# 1-power.net
KiCad netlist of a schematic drawn in Altium Designer
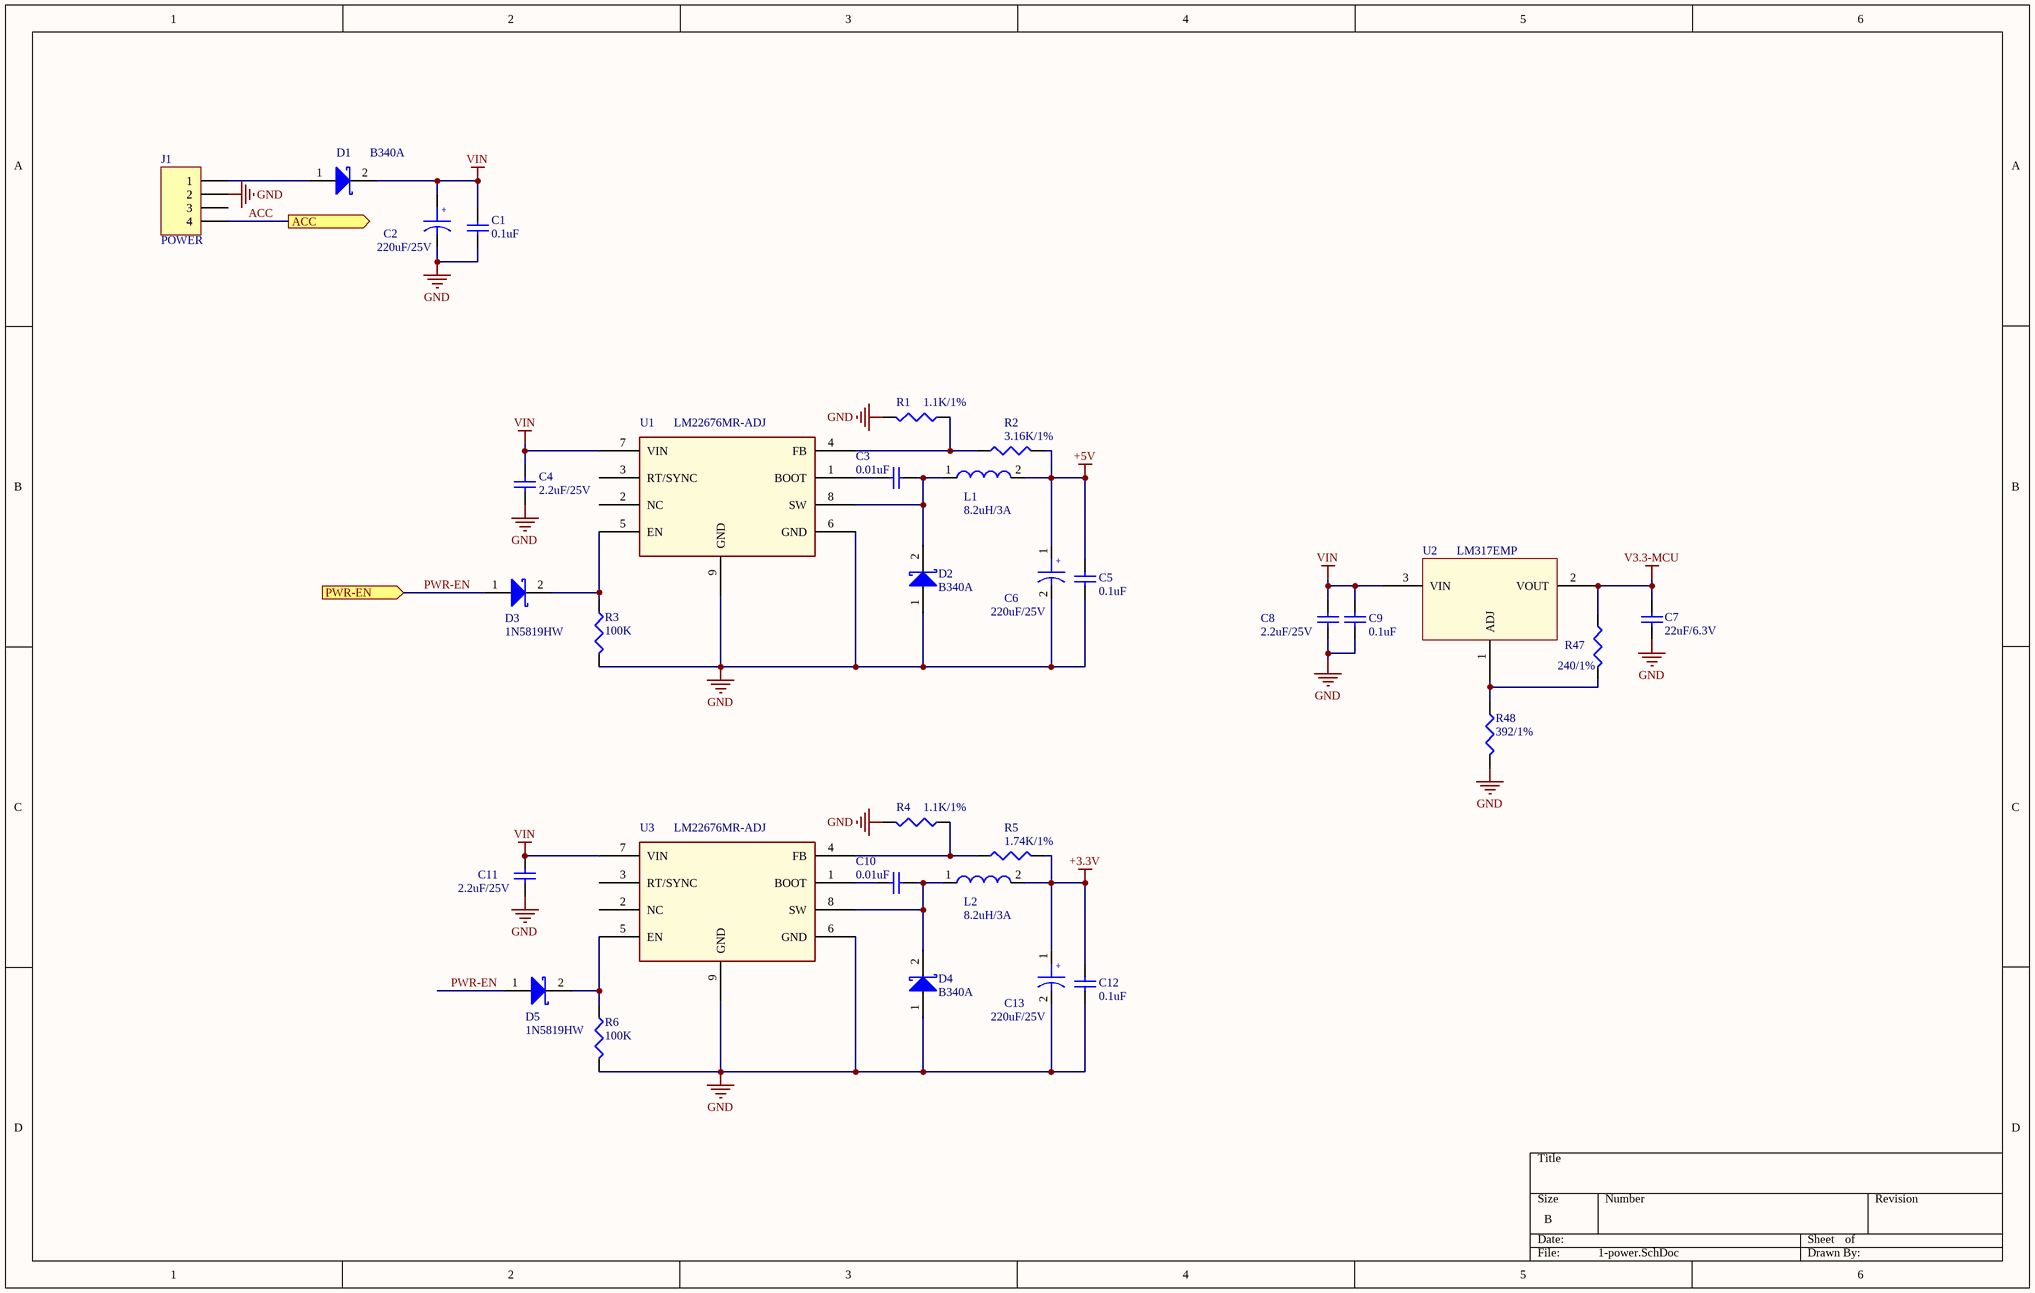
[diagram p0: 1-power.SchDoc]

(export (version "E")
  (design (tool "Eeschema 10.0.6"))
  (components
    (comp (ref "C1")
      (value "0.1uF")
      (footprint "0603")
      (description "Capacitor")
      (fields (field (name "PUBLISHER") "Altium Limited"))
      (libsource (lib "Miscellaneous Devices") (part "Cap"))
    )
    (comp (ref "C2") (value "220uF/25V") (libsource (lib "") (part "CAP WP_1")))
    (comp (ref "C3")
      (value "0.01uF")
      (footprint "0603")
      (description "Capacitor")
      (fields (field (name "PUBLISHER") "Altium Limited"))
      (libsource (lib "Miscellaneous Devices") (part "Cap"))
    )
    (comp (ref "C4")
      (value "2.2uF/25V")
      (footprint "1210")
      (description "Capacitor")
      (fields (field (name "PUBLISHER") "Altium Limited"))
      (libsource (lib "Miscellaneous Devices") (part "Cap"))
    )
    (comp (ref "C5")
      (value "0.1uF")
      (footprint "0603")
      (description "Capacitor")
      (fields (field (name "PUBLISHER") "Altium Limited"))
      (libsource (lib "Miscellaneous Devices") (part "Cap"))
    )
    (comp (ref "C6") (value "220uF/25V") (libsource (lib "*") (part "CAP WP")))
    (comp (ref "C7")
      (value "22uF/6.3V")
      (footprint "1206")
      (description "Capacitor")
      (fields (field (name "PUBLISHER") "Altium Limited"))
      (libsource (lib "Miscellaneous Devices") (part "Cap"))
    )
    (comp (ref "C8")
      (value "2.2uF/25V")
      (footprint "1210")
      (description "Capacitor")
      (fields (field (name "PUBLISHER") "Altium Limited"))
      (libsource (lib "Miscellaneous Devices") (part "Cap"))
    )
    (comp (ref "C9")
      (value "0.1uF")
      (footprint "0603")
      (description "Capacitor")
      (fields (field (name "PUBLISHER") "Altium Limited"))
      (libsource (lib "Miscellaneous Devices") (part "Cap"))
    )
    (comp (ref "C10")
      (value "0.01uF")
      (footprint "0603")
      (description "Capacitor")
      (fields (field (name "PUBLISHER") "Altium Limited"))
      (libsource (lib "Miscellaneous Devices") (part "Cap"))
    )
    (comp (ref "C11")
      (value "2.2uF/25V")
      (footprint "1210")
      (description "Capacitor")
      (fields (field (name "PUBLISHER") "Altium Limited"))
      (libsource (lib "Miscellaneous Devices") (part "Cap"))
    )
    (comp (ref "C12")
      (value "0.1uF")
      (footprint "0603")
      (description "Capacitor")
      (fields (field (name "PUBLISHER") "Altium Limited"))
      (libsource (lib "Miscellaneous Devices") (part "Cap"))
    )
    (comp (ref "C13") (value "220uF/25V") (libsource (lib "*") (part "CAP WP")))
    (comp (ref "D1")
      (value "B340A")
      (footprint "B320A")
      (description "Schottky Rectifier")
      (libsource (lib "Miscellaneous Devices") (part "Diode 11DQ03"))
    )
    (comp (ref "D2")
      (value "B340A")
      (footprint "B320A")
      (description "Schottky Rectifier")
      (libsource (lib "Miscellaneous Devices") (part "Diode 11DQ03"))
    )
    (comp (ref "D3")
      (value "1N5819HW")
      (footprint "1N5819")
      (description "Schottky Rectifier")
      (libsource (lib "Miscellaneous Devices") (part "Diode 11DQ03"))
    )
    (comp (ref "D4")
      (value "B340A")
      (footprint "B320A")
      (description "Schottky Rectifier")
      (libsource (lib "Miscellaneous Devices") (part "Diode 11DQ03"))
    )
    (comp (ref "D5")
      (value "1N5819HW")
      (footprint "1N5819")
      (description "Schottky Rectifier")
      (libsource (lib "Miscellaneous Devices") (part "Diode 11DQ03"))
    )
    (comp (ref "J1")
      (value "POWER")
      (footprint "3030WV-F-2*2P")
      (description "Header, 4-Pin")
      (fields (field (name "PUBLISHER") "Altium Limited"))
      (libsource (lib "Miscellaneous Connectors") (part "Header 4"))
    )
    (comp (ref "L1")
      (value "8.2uH/3A")
      (footprint "IND_8.2UH_3A")
      (fields (field (name "PART NUMBER") "SH00000AJ00"))
      (libsource (lib "*") (part "4.7UH_CDH2D09BNP-4R7MC_0.7A_20%"))
    )
    (comp (ref "L2")
      (value "8.2uH/3A")
      (footprint "IND_8.2UH_3A")
      (fields (field (name "PART NUMBER") "SH00000AJ00"))
      (libsource (lib "*") (part "4.7UH_CDH2D09BNP-4R7MC_0.7A_20%"))
    )
    (comp (ref "R1")
      (value "1.1K/1%")
      (footprint "0603")
      (description "Resistor")
      (fields (field (name "PUBLISHER") "Altium Limited"))
      (libsource (lib "Miscellaneous Devices") (part "Res3"))
    )
    (comp (ref "R2")
      (value "3.16K/1%")
      (footprint "0603")
      (description "Resistor")
      (fields (field (name "PUBLISHER") "Altium Limited"))
      (libsource (lib "Miscellaneous Devices") (part "Res3"))
    )
    (comp (ref "R3")
      (value "100K")
      (footprint "0603")
      (description "Resistor")
      (fields (field (name "PUBLISHER") "Altium Limited"))
      (libsource (lib "Miscellaneous Devices") (part "Res3"))
    )
    (comp (ref "R4")
      (value "1.1K/1%")
      (footprint "0603")
      (description "Resistor")
      (fields (field (name "PUBLISHER") "Altium Limited"))
      (libsource (lib "Miscellaneous Devices") (part "Res3"))
    )
    (comp (ref "R5")
      (value "1.74K/1%")
      (footprint "0603")
      (description "Resistor")
      (fields (field (name "PUBLISHER") "Altium Limited"))
      (libsource (lib "Miscellaneous Devices") (part "Res3"))
    )
    (comp (ref "R6")
      (value "100K")
      (footprint "0603")
      (description "Resistor")
      (fields (field (name "PUBLISHER") "Altium Limited"))
      (libsource (lib "Miscellaneous Devices") (part "Res3"))
    )
    (comp (ref "R47")
      (value "240/1%")
      (footprint "0603")
      (description "Resistor")
      (fields (field (name "PUBLISHER") "Altium Limited"))
      (libsource (lib "Miscellaneous Devices") (part "Res3"))
    )
    (comp (ref "R48")
      (value "392/1%")
      (footprint "0603")
      (description "Resistor")
      (fields (field (name "PUBLISHER") "Altium Limited"))
      (libsource (lib "Miscellaneous Devices") (part "Res3"))
    )
    (comp (ref "U1") (value "LM22676MR-ADJ") (libsource (lib "*") (part "LM22670_0")))
    (comp (ref "U2") (value "LM317EMP") (footprint "SOT-223") (libsource (lib "Schlib") (part "LM317EMP")))
    (comp (ref "U3") (value "LM22676MR-ADJ") (libsource (lib "*") (part "LM22670_0")))
  )
  (nets
    (net (code "1") (name "+3.3V") (class "Default")
      (node (ref "C12") (pin "2") (pinfunction "2_2") (pintype "passive"))
      (node (ref "C13") (pin "1") (pinfunction "1_1") (pintype "passive"))
      (node (ref "L2") (pin "2") (pinfunction "2_2") (pintype "passive"))
      (node (ref "R5") (pin "2") (pinfunction "2_2") (pintype "passive"))
    )
    (net (code "2") (name "+5V") (class "Default")
      (node (ref "C5") (pin "2") (pinfunction "2_2") (pintype "passive"))
      (node (ref "C6") (pin "1") (pinfunction "1_1") (pintype "passive"))
      (node (ref "L1") (pin "2") (pinfunction "2_2") (pintype "passive"))
      (node (ref "R2") (pin "2") (pinfunction "2_2") (pintype "passive"))
    )
    (net (code "3") (name "/ACC") (class "Default")
      (node (ref "J1") (pin "4") (pinfunction "4_4") (pintype "passive"))
    )
    (net (code "4") (name "/PWR-EN") (class "Default")
      (node (ref "D3") (pin "1") (pinfunction "A_1") (pintype "passive"))
      (node (ref "D5") (pin "1") (pinfunction "A_1") (pintype "passive"))
    )
    (net (code "5") (name "GND") (class "Default")
      (node (ref "C1") (pin "1") (pinfunction "1_1") (pintype "passive"))
      (node (ref "C11") (pin "1") (pinfunction "1_1") (pintype "passive"))
      (node (ref "C12") (pin "1") (pinfunction "1_1") (pintype "passive"))
      (node (ref "C13") (pin "2") (pinfunction "2_2") (pintype "passive"))
      (node (ref "C2") (pin "2") (pinfunction "2_2") (pintype "passive"))
      (node (ref "C4") (pin "1") (pinfunction "1_1") (pintype "passive"))
      (node (ref "C5") (pin "1") (pinfunction "1_1") (pintype "passive"))
      (node (ref "C6") (pin "2") (pinfunction "2_2") (pintype "passive"))
      (node (ref "C7") (pin "1") (pinfunction "1_1") (pintype "passive"))
      (node (ref "C8") (pin "1") (pinfunction "1_1") (pintype "passive"))
      (node (ref "C9") (pin "2") (pinfunction "2_2") (pintype "passive"))
      (node (ref "D2") (pin "1") (pinfunction "A_1") (pintype "passive"))
      (node (ref "D4") (pin "1") (pinfunction "A_1") (pintype "passive"))
      (node (ref "J1") (pin "2") (pinfunction "2_2") (pintype "passive"))
      (node (ref "R1") (pin "2") (pinfunction "2_2") (pintype "passive"))
      (node (ref "R3") (pin "2") (pinfunction "2_2") (pintype "passive"))
      (node (ref "R4") (pin "2") (pinfunction "2_2") (pintype "passive"))
      (node (ref "R48") (pin "2") (pinfunction "2_2") (pintype "passive"))
      (node (ref "R6") (pin "2") (pinfunction "2_2") (pintype "passive"))
      (node (ref "U1") (pin "6") (pinfunction "GND_6") (pintype "passive"))
      (node (ref "U1") (pin "9") (pinfunction "GND_9") (pintype "power_in"))
      (node (ref "U3") (pin "6") (pinfunction "GND_6") (pintype "passive"))
      (node (ref "U3") (pin "9") (pinfunction "GND_9") (pintype "power_in"))
    )
    (net (code "6") (name "Net-(D1-A)") (class "Default")
      (node (ref "D1") (pin "1") (pinfunction "A_1") (pintype "passive"))
      (node (ref "J1") (pin "1") (pinfunction "1_1") (pintype "passive"))
    )
    (net (code "7") (name "Net-(D2-K)") (class "Default")
      (node (ref "C3") (pin "1") (pinfunction "1_1") (pintype "passive"))
      (node (ref "D2") (pin "2") (pinfunction "K_2") (pintype "passive"))
      (node (ref "L1") (pin "1") (pinfunction "1_1") (pintype "passive"))
      (node (ref "U1") (pin "8") (pinfunction "SW_8") (pintype "passive"))
    )
    (net (code "8") (name "Net-(D3-K)") (class "Default")
      (node (ref "D3") (pin "2") (pinfunction "K_2") (pintype "passive"))
      (node (ref "R3") (pin "1") (pinfunction "1_1") (pintype "passive"))
      (node (ref "U1") (pin "5") (pinfunction "EN_5") (pintype "passive"))
    )
    (net (code "9") (name "Net-(D4-K)") (class "Default")
      (node (ref "C10") (pin "1") (pinfunction "1_1") (pintype "passive"))
      (node (ref "D4") (pin "2") (pinfunction "K_2") (pintype "passive"))
      (node (ref "L2") (pin "1") (pinfunction "1_1") (pintype "passive"))
      (node (ref "U3") (pin "8") (pinfunction "SW_8") (pintype "passive"))
    )
    (net (code "10") (name "Net-(D5-K)") (class "Default")
      (node (ref "D5") (pin "2") (pinfunction "K_2") (pintype "passive"))
      (node (ref "R6") (pin "1") (pinfunction "1_1") (pintype "passive"))
      (node (ref "U3") (pin "5") (pinfunction "EN_5") (pintype "passive"))
    )
    (net (code "11") (name "Net-(U1-BOOT)") (class "Default")
      (node (ref "C3") (pin "2") (pinfunction "2_2") (pintype "passive"))
      (node (ref "U1") (pin "1") (pinfunction "BOOT_1") (pintype "passive"))
    )
    (net (code "12") (name "Net-(U1-FB)") (class "Default")
      (node (ref "R1") (pin "1") (pinfunction "1_1") (pintype "passive"))
      (node (ref "R2") (pin "1") (pinfunction "1_1") (pintype "passive"))
      (node (ref "U1") (pin "4") (pinfunction "FB_4") (pintype "passive"))
    )
    (net (code "13") (name "Net-(U2-ADJ)") (class "Default")
      (node (ref "R47") (pin "2") (pinfunction "2_2") (pintype "passive"))
      (node (ref "R48") (pin "1") (pinfunction "1_1") (pintype "passive"))
      (node (ref "U2") (pin "1") (pinfunction "ADJ_1") (pintype "passive"))
    )
    (net (code "14") (name "Net-(U3-BOOT)") (class "Default")
      (node (ref "C10") (pin "2") (pinfunction "2_2") (pintype "passive"))
      (node (ref "U3") (pin "1") (pinfunction "BOOT_1") (pintype "passive"))
    )
    (net (code "15") (name "Net-(U3-FB)") (class "Default")
      (node (ref "R4") (pin "1") (pinfunction "1_1") (pintype "passive"))
      (node (ref "R5") (pin "1") (pinfunction "1_1") (pintype "passive"))
      (node (ref "U3") (pin "4") (pinfunction "FB_4") (pintype "passive"))
    )
    (net (code "16") (name "V3.3-MCU") (class "Default")
      (node (ref "C7") (pin "2") (pinfunction "2_2") (pintype "passive"))
      (node (ref "R47") (pin "1") (pinfunction "1_1") (pintype "passive"))
      (node (ref "U2") (pin "2") (pinfunction "VOUT_2") (pintype "passive"))
    )
    (net (code "17") (name "VIN") (class "Default")
      (node (ref "C1") (pin "2") (pinfunction "2_2") (pintype "passive"))
      (node (ref "C11") (pin "2") (pinfunction "2_2") (pintype "passive"))
      (node (ref "C2") (pin "1") (pinfunction "1_1") (pintype "passive"))
      (node (ref "C4") (pin "2") (pinfunction "2_2") (pintype "passive"))
      (node (ref "C8") (pin "2") (pinfunction "2_2") (pintype "passive"))
      (node (ref "C9") (pin "1") (pinfunction "1_1") (pintype "passive"))
      (node (ref "D1") (pin "2") (pinfunction "K_2") (pintype "passive"))
      (node (ref "U1") (pin "7") (pinfunction "VIN_7") (pintype "power_in"))
      (node (ref "U2") (pin "3") (pinfunction "VIN_3") (pintype "passive"))
      (node (ref "U3") (pin "7") (pinfunction "VIN_7") (pintype "power_in"))
    )
    (net (code "18") (name "unconnected-(J1-Pad3)") (class "Default")
      (node (ref "J1") (pin "3") (pinfunction "3_3") (pintype "passive"))
    )
    (net (code "19") (name "unconnected-(U1-NC-Pad2)") (class "Default")
      (node (ref "U1") (pin "2") (pinfunction "NC_2") (pintype "passive"))
    )
    (net (code "20") (name "unconnected-(U1-RT{slash}SYNC-Pad3)") (class "Default")
      (node (ref "U1") (pin "3") (pinfunction "RT/SYNC_3") (pintype "passive"))
    )
    (net (code "21") (name "unconnected-(U3-NC-Pad2)") (class "Default")
      (node (ref "U3") (pin "2") (pinfunction "NC_2") (pintype "passive"))
    )
    (net (code "22") (name "unconnected-(U3-RT{slash}SYNC-Pad3)") (class "Default")
      (node (ref "U3") (pin "3") (pinfunction "RT/SYNC_3") (pintype "passive"))
    )
  )
)
